# untitled.net
KiCad netlist of a schematic drawn in EAGLE
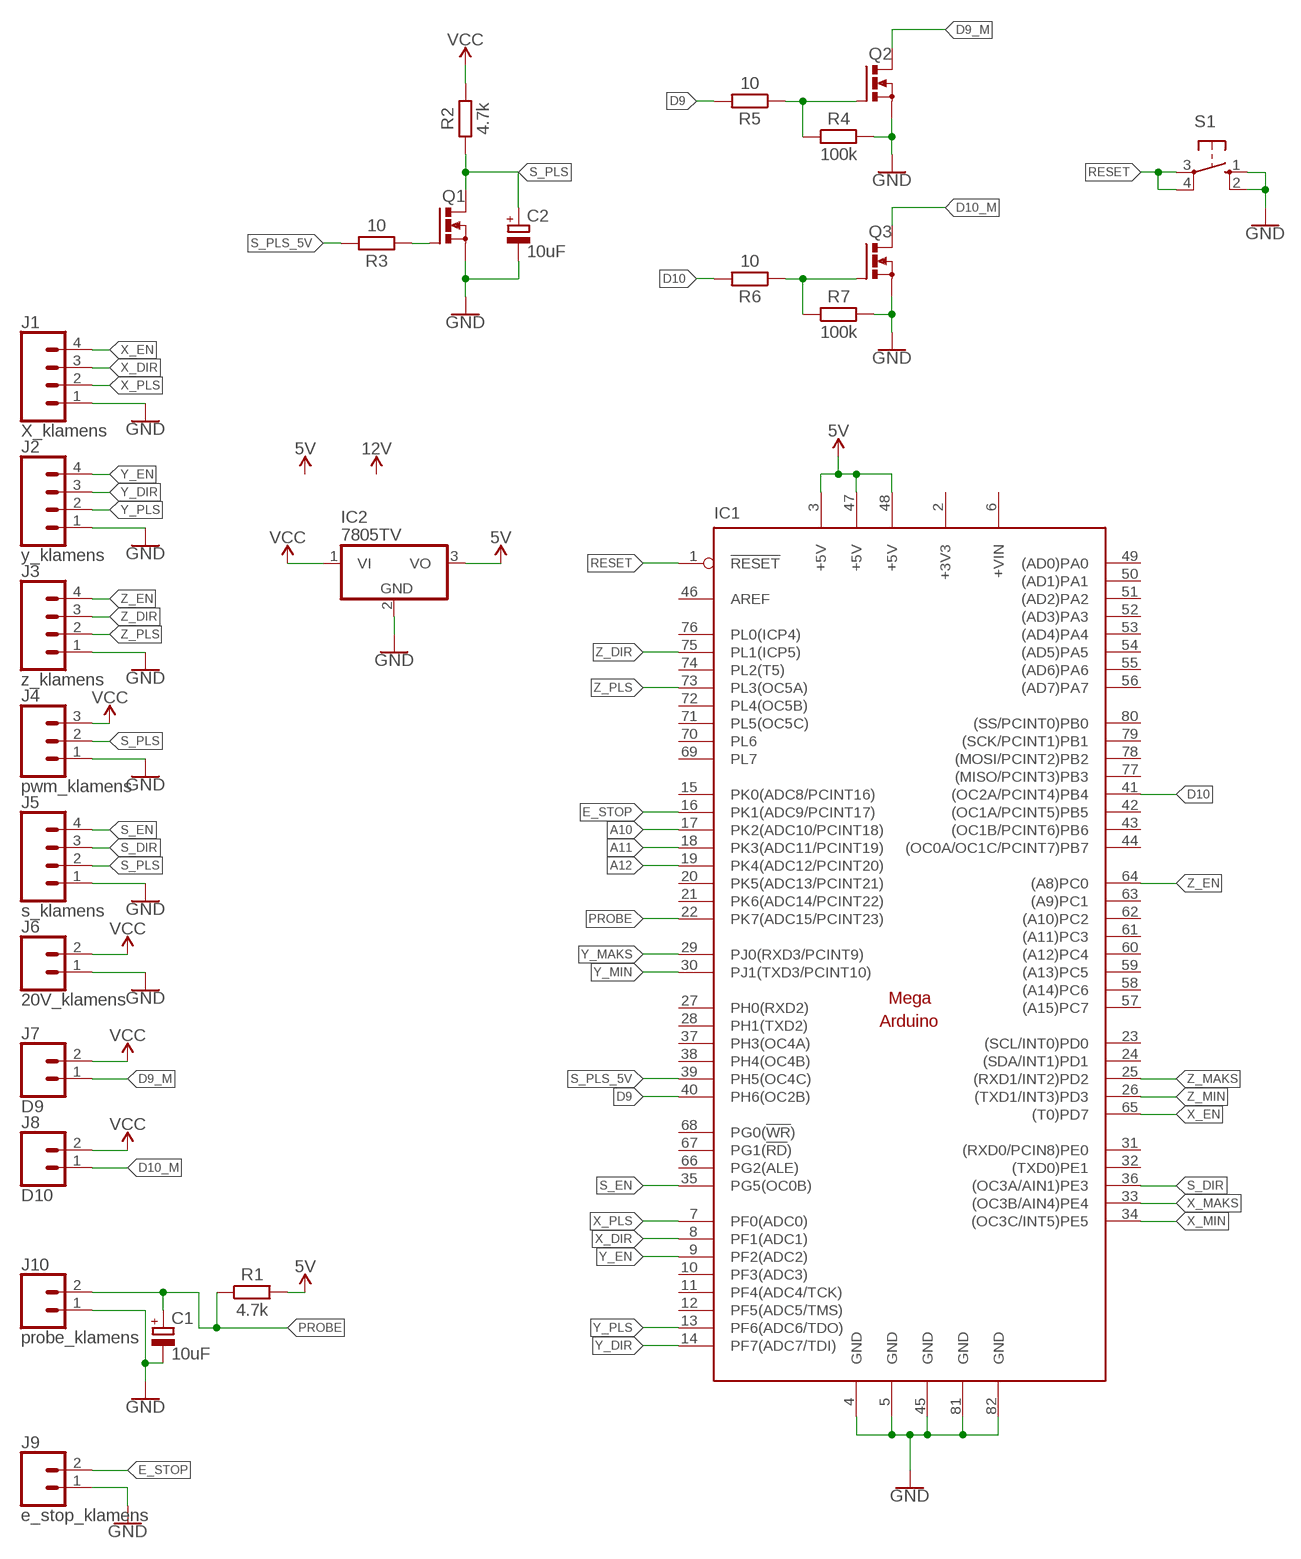
[diagram p0: schematic, sheet 1]

(export (version "E")
  (design (tool "Eeschema 10.0.6"))
  (components
    (comp (ref "C1")
      (value "10uF")
      (footprint "eagle-import:CAPPRD508W65D1000H1100B")
      (libsource (lib "eagle-import") (part "C-POLRADIAL-11MM-DIA_"))
    )
    (comp (ref "C2")
      (value "10uF")
      (footprint "eagle-import:CAPPRD508W65D1000H1100B")
      (libsource (lib "eagle-import") (part "C-POLRADIAL-11MM-DIA_"))
    )
    (comp (ref "IC1")
      (value "MEGAARDUINO_1")
      (footprint "eagle-import:MEGA_ARDUINO")
      (libsource (lib "eagle-import") (part "MEGAARDUINO_1"))
    )
    (comp (ref "IC2")
      (value "7805TV")
      (footprint "eagle-import:TO220V")
      (libsource (lib "eagle-import") (part "78TV05"))
    )
    (comp (ref "J1")
      (value "X_klamens")
      (footprint "eagle-import:SCREWTERMINAL-3.5MM-4_LOCK")
      (libsource (lib "eagle-import") (part "CONN_04SCREW_LOCK"))
    )
    (comp (ref "J2")
      (value "y_klamens")
      (footprint "eagle-import:SCREWTERMINAL-3.5MM-4_LOCK")
      (libsource (lib "eagle-import") (part "CONN_04SCREW_LOCK"))
    )
    (comp (ref "J3")
      (value "z_klamens")
      (footprint "eagle-import:SCREWTERMINAL-3.5MM-4_LOCK")
      (libsource (lib "eagle-import") (part "CONN_04SCREW_LOCK"))
    )
    (comp (ref "J4")
      (value "pwm_klamens")
      (footprint "eagle-import:SCREWTERMINAL-3.5MM-3")
      (libsource (lib "eagle-import") (part "CONN_03SCREW"))
    )
    (comp (ref "J5")
      (value "s_klamens")
      (footprint "eagle-import:SCREWTERMINAL-3.5MM-4_LOCK")
      (libsource (lib "eagle-import") (part "CONN_04SCREW_LOCK"))
    )
    (comp (ref "J6")
      (value "20V_klamens")
      (footprint "eagle-import:SCREWTERMINAL-3.5MM-2_LOCK")
      (libsource (lib "eagle-import") (part "CONN_023.5MM_LOCK"))
    )
    (comp (ref "J7")
      (value "D9")
      (footprint "eagle-import:SCREWTERMINAL-3.5MM-2_LOCK")
      (libsource (lib "eagle-import") (part "CONN_023.5MM_LOCK"))
    )
    (comp (ref "J8")
      (value "D10")
      (footprint "eagle-import:SCREWTERMINAL-3.5MM-2_LOCK")
      (libsource (lib "eagle-import") (part "CONN_023.5MM_LOCK"))
    )
    (comp (ref "J9")
      (value "e_stop_klamens")
      (footprint "eagle-import:SCREWTERMINAL-3.5MM-2_LOCK")
      (libsource (lib "eagle-import") (part "CONN_023.5MM_LOCK"))
    )
    (comp (ref "J10")
      (value "probe_klamens")
      (footprint "eagle-import:SCREWTERMINAL-3.5MM-2_LOCK")
      (libsource (lib "eagle-import") (part "CONN_023.5MM_LOCK"))
    )
    (comp (ref "Q1")
      (value "PMOSFET_NTO220BV")
      (footprint "eagle-import:TO220BV")
      (libsource (lib "eagle-import") (part "PMOSFET_NTO220BV"))
    )
    (comp (ref "Q2")
      (value "PMOSFET_NTO220BV")
      (footprint "eagle-import:TO220BV")
      (libsource (lib "eagle-import") (part "PMOSFET_NTO220BV"))
    )
    (comp (ref "Q3")
      (value "PMOSFET_NTO220BV")
      (footprint "eagle-import:TO220BV")
      (libsource (lib "eagle-import") (part "PMOSFET_NTO220BV"))
    )
    (comp (ref "R1")
      (value "4.7k")
      (footprint "eagle-import:RESAD1176W63L850D250B")
      (libsource (lib "eagle-import") (part "RAXIAL-11.7MM-PITCH_"))
    )
    (comp (ref "R2")
      (value "4.7k")
      (footprint "eagle-import:RESAD1176W63L850D250B")
      (libsource (lib "eagle-import") (part "RAXIAL-11.7MM-PITCH_"))
    )
    (comp (ref "R3")
      (value "10")
      (footprint "eagle-import:RESAD1176W63L850D250B")
      (libsource (lib "eagle-import") (part "RAXIAL-11.7MM-PITCH_"))
    )
    (comp (ref "R4")
      (value "100k")
      (footprint "eagle-import:RESAD1176W63L850D250B")
      (libsource (lib "eagle-import") (part "RAXIAL-11.7MM-PITCH_"))
    )
    (comp (ref "R5")
      (value "10")
      (footprint "eagle-import:RESAD1176W63L850D250B")
      (libsource (lib "eagle-import") (part "RAXIAL-11.7MM-PITCH_"))
    )
    (comp (ref "R6")
      (value "10")
      (footprint "eagle-import:RESAD1176W63L850D250B")
      (libsource (lib "eagle-import") (part "RAXIAL-11.7MM-PITCH_"))
    )
    (comp (ref "R7")
      (value "100k")
      (footprint "eagle-import:RESAD1176W63L850D250B")
      (libsource (lib "eagle-import") (part "RAXIAL-11.7MM-PITCH_"))
    )
    (comp (ref "S1")
      (value "10-XX")
      (footprint "eagle-import:B3F-10XX")
      (fields (field (name "MPN") "B3F-1000"))
      (libsource (lib "eagle-import") (part "10-XX"))
    )
  )
  (nets
    (net (code "1") (name "/+3V3") (class "Default")
      (node (ref "IC1") (pin "2") (pinfunction "+3V3_2") (pintype "power_in"))
    )
    (net (code "2") (name "/+VIN") (class "Default")
      (node (ref "IC1") (pin "6") (pinfunction "+VIN_6") (pintype "power_in"))
    )
    (net (code "3") (name "5V") (class "Default")
      (node (ref "IC1") (pin "3") (pinfunction "+5V_3") (pintype "power_in"))
      (node (ref "IC1") (pin "47") (pinfunction "+5V_47") (pintype "power_in"))
      (node (ref "IC1") (pin "48") (pinfunction "+5V_48") (pintype "power_in"))
      (node (ref "IC2") (pin "3") (pinfunction "VO_3") (pintype "passive"))
      (node (ref "R1") (pin "2") (pinfunction "2_2") (pintype "passive"))
    )
    (net (code "5") (name "A10") (class "Default")
      (node (ref "IC1") (pin "17") (pinfunction "PK2(ADC10/PCINT18)_17") (pintype "bidirectional"))
    )
    (net (code "6") (name "A11") (class "Default")
      (node (ref "IC1") (pin "18") (pinfunction "PK3(ADC11/PCINT19)_18") (pintype "bidirectional"))
    )
    (net (code "7") (name "A12") (class "Default")
      (node (ref "IC1") (pin "19") (pinfunction "PK4(ADC12/PCINT20)_19") (pintype "bidirectional"))
    )
    (net (code "8") (name "D9") (class "Default")
      (node (ref "IC1") (pin "40") (pinfunction "PH6(OC2B)_40") (pintype "bidirectional"))
      (node (ref "R5") (pin "2") (pinfunction "2_2") (pintype "passive"))
    )
    (net (code "9") (name "D9_M") (class "Default")
      (node (ref "J7") (pin "1") (pinfunction "1_1") (pintype "passive"))
      (node (ref "Q2") (pin "D") (pinfunction "D_D") (pintype "passive"))
    )
    (net (code "10") (name "D10") (class "Default")
      (node (ref "IC1") (pin "41") (pinfunction "(OC2A/PCINT4)PB4_41") (pintype "bidirectional"))
      (node (ref "R6") (pin "2") (pinfunction "2_2") (pintype "passive"))
    )
    (net (code "11") (name "D10_M") (class "Default")
      (node (ref "J8") (pin "1") (pinfunction "1_1") (pintype "passive"))
      (node (ref "Q3") (pin "D") (pinfunction "D_D") (pintype "passive"))
    )
    (net (code "12") (name "E_STOP") (class "Default")
      (node (ref "IC1") (pin "16") (pinfunction "PK1(ADC9/PCINT17)_16") (pintype "bidirectional"))
      (node (ref "J9") (pin "2") (pinfunction "2_2") (pintype "passive"))
    )
    (net (code "13") (name "GND") (class "Default")
      (node (ref "C1") (pin "2") (pinfunction "-_2") (pintype "passive"))
      (node (ref "C2") (pin "2") (pinfunction "-_2") (pintype "passive"))
      (node (ref "IC1") (pin "4") (pinfunction "GND_4") (pintype "power_in"))
      (node (ref "IC1") (pin "45") (pinfunction "GND_45") (pintype "power_in"))
      (node (ref "IC1") (pin "5") (pinfunction "GND_5") (pintype "power_in"))
      (node (ref "IC1") (pin "81") (pinfunction "GND_81") (pintype "power_in"))
      (node (ref "IC1") (pin "82") (pinfunction "GND_82") (pintype "power_in"))
      (node (ref "IC2") (pin "2") (pinfunction "GND_2") (pintype "passive"))
      (node (ref "J1") (pin "1") (pinfunction "1_1") (pintype "passive"))
      (node (ref "J10") (pin "1") (pinfunction "1_1") (pintype "passive"))
      (node (ref "J2") (pin "1") (pinfunction "1_1") (pintype "passive"))
      (node (ref "J3") (pin "1") (pinfunction "1_1") (pintype "passive"))
      (node (ref "J4") (pin "1") (pinfunction "1_1") (pintype "passive"))
      (node (ref "J5") (pin "1") (pinfunction "1_1") (pintype "passive"))
      (node (ref "J6") (pin "1") (pinfunction "1_1") (pintype "passive"))
      (node (ref "J9") (pin "1") (pinfunction "1_1") (pintype "passive"))
      (node (ref "Q1") (pin "S") (pinfunction "S_S") (pintype "passive"))
      (node (ref "Q2") (pin "S") (pinfunction "S_S") (pintype "passive"))
      (node (ref "Q3") (pin "S") (pinfunction "S_S") (pintype "passive"))
      (node (ref "R4") (pin "2") (pinfunction "2_2") (pintype "passive"))
      (node (ref "R7") (pin "2") (pinfunction "2_2") (pintype "passive"))
      (node (ref "S1") (pin "1") (pinfunction "S_1") (pintype "passive"))
      (node (ref "S1") (pin "2") (pinfunction "S1_2") (pintype "passive"))
    )
    (net (code "14") (name "Net-(Q1-PadG)") (class "Default")
      (node (ref "Q1") (pin "G") (pinfunction "G_G") (pintype "passive"))
      (node (ref "R3") (pin "1") (pinfunction "1_1") (pintype "passive"))
    )
    (net (code "15") (name "Net-(Q2-PadG)") (class "Default")
      (node (ref "Q2") (pin "G") (pinfunction "G_G") (pintype "passive"))
      (node (ref "R4") (pin "1") (pinfunction "1_1") (pintype "passive"))
      (node (ref "R5") (pin "1") (pinfunction "1_1") (pintype "passive"))
    )
    (net (code "16") (name "Net-(Q3-PadG)") (class "Default")
      (node (ref "Q3") (pin "G") (pinfunction "G_G") (pintype "passive"))
      (node (ref "R6") (pin "1") (pinfunction "1_1") (pintype "passive"))
      (node (ref "R7") (pin "1") (pinfunction "1_1") (pintype "passive"))
    )
    (net (code "17") (name "PROBE") (class "Default")
      (node (ref "C1") (pin "1") (pinfunction "+_1") (pintype "passive"))
      (node (ref "IC1") (pin "22") (pinfunction "PK7(ADC15/PCINT23)_22") (pintype "bidirectional"))
      (node (ref "J10") (pin "2") (pinfunction "2_2") (pintype "passive"))
      (node (ref "R1") (pin "1") (pinfunction "1_1") (pintype "passive"))
    )
    (net (code "18") (name "RESET") (class "Default")
      (node (ref "IC1") (pin "1") (pinfunction "~{RESET}_1") (pintype "bidirectional"))
      (node (ref "S1") (pin "3") (pinfunction "P_3") (pintype "passive"))
      (node (ref "S1") (pin "4") (pinfunction "P1_4") (pintype "passive"))
    )
    (net (code "19") (name "S_DIR") (class "Default")
      (node (ref "IC1") (pin "36") (pinfunction "(OC3A/AIN1)PE3_36") (pintype "bidirectional"))
      (node (ref "J5") (pin "3") (pinfunction "3_3") (pintype "passive"))
    )
    (net (code "20") (name "S_EN") (class "Default")
      (node (ref "IC1") (pin "35") (pinfunction "PG5(OC0B)_35") (pintype "bidirectional"))
      (node (ref "J5") (pin "4") (pinfunction "4_4") (pintype "passive"))
    )
    (net (code "21") (name "S_PLS") (class "Default")
      (node (ref "C2") (pin "1") (pinfunction "+_1") (pintype "passive"))
      (node (ref "J4") (pin "2") (pinfunction "2_2") (pintype "passive"))
      (node (ref "J5") (pin "2") (pinfunction "2_2") (pintype "passive"))
      (node (ref "Q1") (pin "D") (pinfunction "D_D") (pintype "passive"))
      (node (ref "R2") (pin "1") (pinfunction "1_1") (pintype "passive"))
    )
    (net (code "22") (name "S_PLS_5V") (class "Default")
      (node (ref "IC1") (pin "39") (pinfunction "PH5(OC4C)_39") (pintype "bidirectional"))
      (node (ref "R3") (pin "2") (pinfunction "2_2") (pintype "passive"))
    )
    (net (code "23") (name "VCC") (class "Default")
      (node (ref "IC2") (pin "1") (pinfunction "VI_1") (pintype "input"))
      (node (ref "J4") (pin "3") (pinfunction "3_3") (pintype "passive"))
      (node (ref "J6") (pin "2") (pinfunction "2_2") (pintype "passive"))
      (node (ref "J7") (pin "2") (pinfunction "2_2") (pintype "passive"))
      (node (ref "J8") (pin "2") (pinfunction "2_2") (pintype "passive"))
      (node (ref "R2") (pin "2") (pinfunction "2_2") (pintype "passive"))
    )
    (net (code "24") (name "X_DIR") (class "Default")
      (node (ref "IC1") (pin "8") (pinfunction "PF1(ADC1)_8") (pintype "bidirectional"))
      (node (ref "J1") (pin "3") (pinfunction "3_3") (pintype "passive"))
    )
    (net (code "25") (name "X_EN") (class "Default")
      (node (ref "IC1") (pin "65") (pinfunction "(T0)PD7_65") (pintype "bidirectional"))
      (node (ref "J1") (pin "4") (pinfunction "4_4") (pintype "passive"))
    )
    (net (code "26") (name "X_MAKS") (class "Default")
      (node (ref "IC1") (pin "33") (pinfunction "(OC3B/AIN4)PE4_33") (pintype "bidirectional"))
    )
    (net (code "27") (name "X_MIN") (class "Default")
      (node (ref "IC1") (pin "34") (pinfunction "(OC3C/INT5)PE5_34") (pintype "bidirectional"))
    )
    (net (code "28") (name "X_PLS") (class "Default")
      (node (ref "IC1") (pin "7") (pinfunction "PF0(ADC0)_7") (pintype "bidirectional"))
      (node (ref "J1") (pin "2") (pinfunction "2_2") (pintype "passive"))
    )
    (net (code "29") (name "Y_DIR") (class "Default")
      (node (ref "IC1") (pin "14") (pinfunction "PF7(ADC7/TDI)_14") (pintype "bidirectional"))
      (node (ref "J2") (pin "3") (pinfunction "3_3") (pintype "passive"))
    )
    (net (code "30") (name "Y_EN") (class "Default")
      (node (ref "IC1") (pin "9") (pinfunction "PF2(ADC2)_9") (pintype "bidirectional"))
      (node (ref "J2") (pin "4") (pinfunction "4_4") (pintype "passive"))
    )
    (net (code "31") (name "Y_MAKS") (class "Default")
      (node (ref "IC1") (pin "29") (pinfunction "PJ0(RXD3/PCINT9)_29") (pintype "bidirectional"))
    )
    (net (code "32") (name "Y_MIN") (class "Default")
      (node (ref "IC1") (pin "30") (pinfunction "PJ1(TXD3/PCINT10)_30") (pintype "bidirectional"))
    )
    (net (code "33") (name "Y_PLS") (class "Default")
      (node (ref "IC1") (pin "13") (pinfunction "PF6(ADC6/TDO)_13") (pintype "bidirectional"))
      (node (ref "J2") (pin "2") (pinfunction "2_2") (pintype "passive"))
    )
    (net (code "34") (name "Z_DIR") (class "Default")
      (node (ref "IC1") (pin "75") (pinfunction "PL1(ICP5)_75") (pintype "bidirectional"))
      (node (ref "J3") (pin "3") (pinfunction "3_3") (pintype "passive"))
    )
    (net (code "35") (name "Z_EN") (class "Default")
      (node (ref "IC1") (pin "64") (pinfunction "(A8)PC0_64") (pintype "bidirectional"))
      (node (ref "J3") (pin "4") (pinfunction "4_4") (pintype "passive"))
    )
    (net (code "36") (name "Z_MAKS") (class "Default")
      (node (ref "IC1") (pin "25") (pinfunction "(RXD1/INT2)PD2_25") (pintype "bidirectional"))
    )
    (net (code "37") (name "Z_MIN") (class "Default")
      (node (ref "IC1") (pin "26") (pinfunction "(TXD1/INT3)PD3_26") (pintype "bidirectional"))
    )
    (net (code "38") (name "Z_PLS") (class "Default")
      (node (ref "IC1") (pin "73") (pinfunction "PL3(OC5A)_73") (pintype "bidirectional"))
      (node (ref "J3") (pin "2") (pinfunction "2_2") (pintype "passive"))
    )
    (net (code "39") (name "unconnected-(IC1-(A9)PC1-Pad63)") (class "Default")
      (node (ref "IC1") (pin "63") (pinfunction "(A9)PC1_63") (pintype "bidirectional"))
    )
    (net (code "40") (name "unconnected-(IC1-(A10)PC2-Pad62)") (class "Default")
      (node (ref "IC1") (pin "62") (pinfunction "(A10)PC2_62") (pintype "bidirectional"))
    )
    (net (code "41") (name "unconnected-(IC1-(A11)PC3-Pad61)") (class "Default")
      (node (ref "IC1") (pin "61") (pinfunction "(A11)PC3_61") (pintype "bidirectional"))
    )
    (net (code "42") (name "unconnected-(IC1-(A12)PC4-Pad60)") (class "Default")
      (node (ref "IC1") (pin "60") (pinfunction "(A12)PC4_60") (pintype "bidirectional"))
    )
    (net (code "43") (name "unconnected-(IC1-(A13)PC5-Pad59)") (class "Default")
      (node (ref "IC1") (pin "59") (pinfunction "(A13)PC5_59") (pintype "bidirectional"))
    )
    (net (code "44") (name "unconnected-(IC1-(A14)PC6-Pad58)") (class "Default")
      (node (ref "IC1") (pin "58") (pinfunction "(A14)PC6_58") (pintype "bidirectional"))
    )
    (net (code "45") (name "unconnected-(IC1-(A15)PC7-Pad57)") (class "Default")
      (node (ref "IC1") (pin "57") (pinfunction "(A15)PC7_57") (pintype "bidirectional"))
    )
    (net (code "46") (name "unconnected-(IC1-(AD0)PA0-Pad49)") (class "Default")
      (node (ref "IC1") (pin "49") (pinfunction "(AD0)PA0_49") (pintype "bidirectional"))
    )
    (net (code "47") (name "unconnected-(IC1-(AD1)PA1-Pad50)") (class "Default")
      (node (ref "IC1") (pin "50") (pinfunction "(AD1)PA1_50") (pintype "bidirectional"))
    )
    (net (code "48") (name "unconnected-(IC1-(AD2)PA2-Pad51)") (class "Default")
      (node (ref "IC1") (pin "51") (pinfunction "(AD2)PA2_51") (pintype "bidirectional"))
    )
    (net (code "49") (name "unconnected-(IC1-(AD3)PA3-Pad52)") (class "Default")
      (node (ref "IC1") (pin "52") (pinfunction "(AD3)PA3_52") (pintype "bidirectional"))
    )
    (net (code "50") (name "unconnected-(IC1-(AD4)PA4-Pad53)") (class "Default")
      (node (ref "IC1") (pin "53") (pinfunction "(AD4)PA4_53") (pintype "bidirectional"))
    )
    (net (code "51") (name "unconnected-(IC1-(AD5)PA5-Pad54)") (class "Default")
      (node (ref "IC1") (pin "54") (pinfunction "(AD5)PA5_54") (pintype "bidirectional"))
    )
    (net (code "52") (name "unconnected-(IC1-(AD6)PA6-Pad55)") (class "Default")
      (node (ref "IC1") (pin "55") (pinfunction "(AD6)PA6_55") (pintype "bidirectional"))
    )
    (net (code "53") (name "unconnected-(IC1-(AD7)PA7-Pad56)") (class "Default")
      (node (ref "IC1") (pin "56") (pinfunction "(AD7)PA7_56") (pintype "bidirectional"))
    )
    (net (code "54") (name "unconnected-(IC1-(MISO{slash}PCINT3)PB3-Pad77)") (class "Default")
      (node (ref "IC1") (pin "77") (pinfunction "(MISO/PCINT3)PB3_77") (pintype "bidirectional"))
    )
    (net (code "55") (name "unconnected-(IC1-(MOSI{slash}PCINT2)PB2-Pad78)") (class "Default")
      (node (ref "IC1") (pin "78") (pinfunction "(MOSI/PCINT2)PB2_78") (pintype "bidirectional"))
    )
    (net (code "56") (name "unconnected-(IC1-(OC0A{slash}OC1C{slash}PCINT7)PB7-Pad44)") (class "Default")
      (node (ref "IC1") (pin "44") (pinfunction "(OC0A/OC1C/PCINT7)PB7_44") (pintype "bidirectional"))
    )
    (net (code "57") (name "unconnected-(IC1-(OC1A{slash}PCINT5)PB5-Pad42)") (class "Default")
      (node (ref "IC1") (pin "42") (pinfunction "(OC1A/PCINT5)PB5_42") (pintype "bidirectional"))
    )
    (net (code "58") (name "unconnected-(IC1-(OC1B{slash}PCINT6)PB6-Pad43)") (class "Default")
      (node (ref "IC1") (pin "43") (pinfunction "(OC1B/PCINT6)PB6_43") (pintype "bidirectional"))
    )
    (net (code "59") (name "unconnected-(IC1-(RXD0{slash}PCIN8)PE0-Pad31)") (class "Default")
      (node (ref "IC1") (pin "31") (pinfunction "(RXD0/PCIN8)PE0_31") (pintype "bidirectional"))
    )
    (net (code "60") (name "unconnected-(IC1-(SCK{slash}PCINT1)PB1-Pad79)") (class "Default")
      (node (ref "IC1") (pin "79") (pinfunction "(SCK/PCINT1)PB1_79") (pintype "bidirectional"))
    )
    (net (code "61") (name "unconnected-(IC1-(SCL{slash}INT0)PD0-Pad23)") (class "Default")
      (node (ref "IC1") (pin "23") (pinfunction "(SCL/INT0)PD0_23") (pintype "bidirectional"))
    )
    (net (code "62") (name "unconnected-(IC1-(SDA{slash}INT1)PD1-Pad24)") (class "Default")
      (node (ref "IC1") (pin "24") (pinfunction "(SDA/INT1)PD1_24") (pintype "bidirectional"))
    )
    (net (code "63") (name "unconnected-(IC1-(SS{slash}PCINT0)PB0-Pad80)") (class "Default")
      (node (ref "IC1") (pin "80") (pinfunction "(SS/PCINT0)PB0_80") (pintype "bidirectional"))
    )
    (net (code "64") (name "unconnected-(IC1-(TXD0)PE1-Pad32)") (class "Default")
      (node (ref "IC1") (pin "32") (pinfunction "(TXD0)PE1_32") (pintype "bidirectional"))
    )
    (net (code "65") (name "unconnected-(IC1-AREF-Pad46)") (class "Default")
      (node (ref "IC1") (pin "46") (pinfunction "AREF_46") (pintype "bidirectional"))
    )
    (net (code "66") (name "unconnected-(IC1-PF3(ADC3)-Pad10)") (class "Default")
      (node (ref "IC1") (pin "10") (pinfunction "PF3(ADC3)_10") (pintype "bidirectional"))
    )
    (net (code "67") (name "unconnected-(IC1-PF4(ADC4{slash}TCK)-Pad11)") (class "Default")
      (node (ref "IC1") (pin "11") (pinfunction "PF4(ADC4/TCK)_11") (pintype "bidirectional"))
    )
    (net (code "68") (name "unconnected-(IC1-PF5(ADC5{slash}TMS)-Pad12)") (class "Default")
      (node (ref "IC1") (pin "12") (pinfunction "PF5(ADC5/TMS)_12") (pintype "bidirectional"))
    )
    (net (code "69") (name "unconnected-(IC1-PG0(~{WR})-Pad68)") (class "Default")
      (node (ref "IC1") (pin "68") (pinfunction "PG0(~{WR})_68") (pintype "bidirectional"))
    )
    (net (code "70") (name "unconnected-(IC1-PG1(~{RD})-Pad67)") (class "Default")
      (node (ref "IC1") (pin "67") (pinfunction "PG1(~{RD})_67") (pintype "bidirectional"))
    )
    (net (code "71") (name "unconnected-(IC1-PG2(ALE)-Pad66)") (class "Default")
      (node (ref "IC1") (pin "66") (pinfunction "PG2(ALE)_66") (pintype "bidirectional"))
    )
    (net (code "72") (name "unconnected-(IC1-PH0(RXD2)-Pad27)") (class "Default")
      (node (ref "IC1") (pin "27") (pinfunction "PH0(RXD2)_27") (pintype "bidirectional"))
    )
    (net (code "73") (name "unconnected-(IC1-PH1(TXD2)-Pad28)") (class "Default")
      (node (ref "IC1") (pin "28") (pinfunction "PH1(TXD2)_28") (pintype "bidirectional"))
    )
    (net (code "74") (name "unconnected-(IC1-PH3(OC4A)-Pad37)") (class "Default")
      (node (ref "IC1") (pin "37") (pinfunction "PH3(OC4A)_37") (pintype "bidirectional"))
    )
    (net (code "75") (name "unconnected-(IC1-PH4(OC4B)-Pad38)") (class "Default")
      (node (ref "IC1") (pin "38") (pinfunction "PH4(OC4B)_38") (pintype "bidirectional"))
    )
    (net (code "76") (name "unconnected-(IC1-PK0(ADC8{slash}PCINT16)-Pad15)") (class "Default")
      (node (ref "IC1") (pin "15") (pinfunction "PK0(ADC8/PCINT16)_15") (pintype "bidirectional"))
    )
    (net (code "77") (name "unconnected-(IC1-PK5(ADC13{slash}PCINT21)-Pad20)") (class "Default")
      (node (ref "IC1") (pin "20") (pinfunction "PK5(ADC13/PCINT21)_20") (pintype "bidirectional"))
    )
    (net (code "78") (name "unconnected-(IC1-PK6(ADC14{slash}PCINT22)-Pad21)") (class "Default")
      (node (ref "IC1") (pin "21") (pinfunction "PK6(ADC14/PCINT22)_21") (pintype "bidirectional"))
    )
    (net (code "79") (name "unconnected-(IC1-PL0(ICP4)-Pad76)") (class "Default")
      (node (ref "IC1") (pin "76") (pinfunction "PL0(ICP4)_76") (pintype "bidirectional"))
    )
    (net (code "80") (name "unconnected-(IC1-PL2(T5)-Pad74)") (class "Default")
      (node (ref "IC1") (pin "74") (pinfunction "PL2(T5)_74") (pintype "bidirectional"))
    )
    (net (code "81") (name "unconnected-(IC1-PL4(OC5B)-Pad72)") (class "Default")
      (node (ref "IC1") (pin "72") (pinfunction "PL4(OC5B)_72") (pintype "bidirectional"))
    )
    (net (code "82") (name "unconnected-(IC1-PL5(OC5C)-Pad71)") (class "Default")
      (node (ref "IC1") (pin "71") (pinfunction "PL5(OC5C)_71") (pintype "bidirectional"))
    )
    (net (code "83") (name "unconnected-(IC1-PL6-Pad70)") (class "Default")
      (node (ref "IC1") (pin "70") (pinfunction "PL6_70") (pintype "bidirectional"))
    )
    (net (code "84") (name "unconnected-(IC1-PL7-Pad69)") (class "Default")
      (node (ref "IC1") (pin "69") (pinfunction "PL7_69") (pintype "bidirectional"))
    )
  )
)
